# inductionlooper.net
KiCad netlist of a schematic drawn in EAGLE
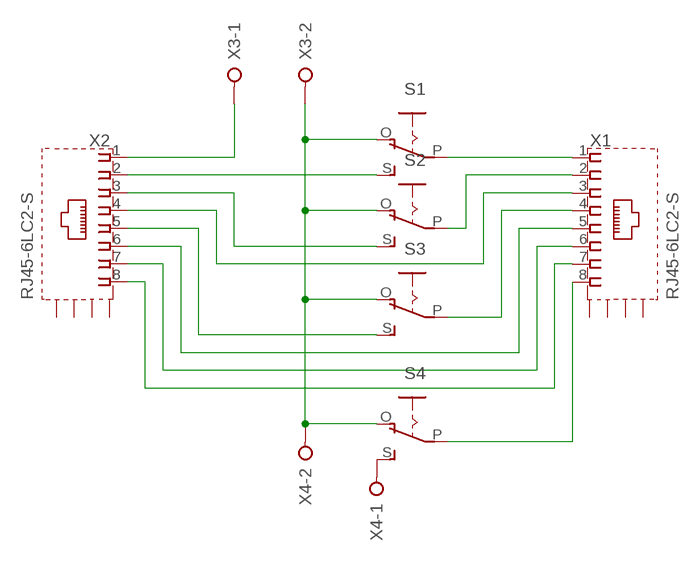
[diagram p0: schematic, sheet 1]

(export (version "E")
  (design (tool "Eeschema 10.0.6"))
  (components
    (comp (ref "S1")
      (value "EG1218S")
      (footprint "eagle-import:EG1218")
      (libsource (lib "eagle-import") (part "EG1218S"))
    )
    (comp (ref "S2")
      (value "EG1218S")
      (footprint "eagle-import:EG1218")
      (libsource (lib "eagle-import") (part "EG1218S"))
    )
    (comp (ref "S3")
      (value "EG1218S")
      (footprint "eagle-import:EG1218")
      (libsource (lib "eagle-import") (part "EG1218S"))
    )
    (comp (ref "S4")
      (value "EG1218S")
      (footprint "eagle-import:EG1218")
      (libsource (lib "eagle-import") (part "EG1218S"))
    )
    (comp (ref "X1")
      (value "RJ45-6LC2-S")
      (footprint "eagle-import:RJ45-SHIELD2")
      (libsource (lib "eagle-import") (part "RJ452-S-6LC"))
    )
    (comp (ref "X2")
      (value "RJ45-6LC2-S")
      (footprint "eagle-import:RJ45-SHIELD2")
      (libsource (lib "eagle-import") (part "RJ452-S-6LC"))
    )
    (comp (ref "X3")
      (value "W237-02P")
      (footprint "eagle-import:W237-132")
      (libsource (lib "eagle-import") (part "W237-02P"))
    )
    (comp (ref "X4")
      (value "W237-02P")
      (footprint "eagle-import:W237-132")
      (libsource (lib "eagle-import") (part "W237-02P"))
    )
  )
  (nets
    (net (code "1") (name "Net-(S1-PadP)") (class "Default")
      (node (ref "S1") (pin "P") (pinfunction "P_P") (pintype "passive"))
      (node (ref "X1") (pin "1") (pinfunction "1_1") (pintype "passive"))
    )
    (net (code "2") (name "Net-(S1-PadS)") (class "Default")
      (node (ref "S1") (pin "S") (pinfunction "S_S") (pintype "passive"))
      (node (ref "X2") (pin "2") (pinfunction "2_2") (pintype "passive"))
    )
    (net (code "3") (name "Net-(S2-PadP)") (class "Default")
      (node (ref "S2") (pin "P") (pinfunction "P_P") (pintype "passive"))
      (node (ref "X1") (pin "2") (pinfunction "2_2") (pintype "passive"))
    )
    (net (code "4") (name "Net-(S2-PadS)") (class "Default")
      (node (ref "S2") (pin "S") (pinfunction "S_S") (pintype "passive"))
      (node (ref "X2") (pin "3") (pinfunction "3_3") (pintype "passive"))
    )
    (net (code "5") (name "Net-(S3-PadP)") (class "Default")
      (node (ref "S3") (pin "P") (pinfunction "P_P") (pintype "passive"))
      (node (ref "X1") (pin "4") (pinfunction "4_4") (pintype "passive"))
    )
    (net (code "6") (name "Net-(S3-PadS)") (class "Default")
      (node (ref "S3") (pin "S") (pinfunction "S_S") (pintype "passive"))
      (node (ref "X2") (pin "5") (pinfunction "5_5") (pintype "passive"))
    )
    (net (code "7") (name "Net-(S4-PadP)") (class "Default")
      (node (ref "S4") (pin "P") (pinfunction "P_P") (pintype "passive"))
      (node (ref "X1") (pin "8") (pinfunction "8_8") (pintype "passive"))
    )
    (net (code "8") (name "Net-(X1-Pad3)") (class "Default")
      (node (ref "X1") (pin "3") (pinfunction "3_3") (pintype "passive"))
      (node (ref "X2") (pin "4") (pinfunction "4_4") (pintype "passive"))
    )
    (net (code "9") (name "Net-(X1-Pad5)") (class "Default")
      (node (ref "X1") (pin "5") (pinfunction "5_5") (pintype "passive"))
      (node (ref "X2") (pin "6") (pinfunction "6_6") (pintype "passive"))
    )
    (net (code "10") (name "Net-(X1-Pad6)") (class "Default")
      (node (ref "X1") (pin "6") (pinfunction "6_6") (pintype "passive"))
      (node (ref "X2") (pin "7") (pinfunction "7_7") (pintype "passive"))
    )
    (net (code "11") (name "Net-(X1-Pad7)") (class "Default")
      (node (ref "X1") (pin "7") (pinfunction "7_7") (pintype "passive"))
      (node (ref "X2") (pin "8") (pinfunction "8_8") (pintype "passive"))
    )
    (net (code "12") (name "Net-(X3A-KL)") (class "Default")
      (node (ref "X2") (pin "1") (pinfunction "1_1") (pintype "passive"))
      (node (ref "X3") (pin "1") (pinfunction "KL_1") (pintype "passive"))
    )
    (net (code "13") (name "Net-(X3B-KL)") (class "Default")
      (node (ref "S1") (pin "O") (pinfunction "O_O") (pintype "passive"))
      (node (ref "S2") (pin "O") (pinfunction "O_O") (pintype "passive"))
      (node (ref "S3") (pin "O") (pinfunction "O_O") (pintype "passive"))
      (node (ref "S4") (pin "O") (pinfunction "O_O") (pintype "passive"))
      (node (ref "X3") (pin "2") (pinfunction "KL_2") (pintype "passive"))
      (node (ref "X4") (pin "2") (pinfunction "KL_2") (pintype "passive"))
    )
    (net (code "14") (name "Net-(X4A-KL)") (class "Default")
      (node (ref "S4") (pin "S") (pinfunction "S_S") (pintype "passive"))
      (node (ref "X4") (pin "1") (pinfunction "KL_1") (pintype "passive"))
    )
    (net (code "15") (name "unconnected-(X1-S-PadS1)") (class "Default")
      (node (ref "X1") (pin "S1") (pinfunction "S_S1") (pintype "passive"))
    )
    (net (code "16") (name "unconnected-(X1-S-PadS2)") (class "Default")
      (node (ref "X1") (pin "S2") (pinfunction "S_S2") (pintype "passive"))
    )
    (net (code "17") (name "unconnected-(X1-S-PadS3)") (class "Default")
      (node (ref "X1") (pin "S3") (pinfunction "S_S3") (pintype "passive"))
    )
    (net (code "18") (name "unconnected-(X1-S-PadS4)") (class "Default")
      (node (ref "X1") (pin "S4") (pinfunction "S_S4") (pintype "passive"))
    )
    (net (code "19") (name "unconnected-(X2-S-PadS1)") (class "Default")
      (node (ref "X2") (pin "S1") (pinfunction "S_S1") (pintype "passive"))
    )
    (net (code "20") (name "unconnected-(X2-S-PadS2)") (class "Default")
      (node (ref "X2") (pin "S2") (pinfunction "S_S2") (pintype "passive"))
    )
    (net (code "21") (name "unconnected-(X2-S-PadS3)") (class "Default")
      (node (ref "X2") (pin "S3") (pinfunction "S_S3") (pintype "passive"))
    )
    (net (code "22") (name "unconnected-(X2-S-PadS4)") (class "Default")
      (node (ref "X2") (pin "S4") (pinfunction "S_S4") (pintype "passive"))
    )
  )
)
